# STSPIN32F0A_ESC2.net
KiCad netlist of a schematic drawn in Altium Designer
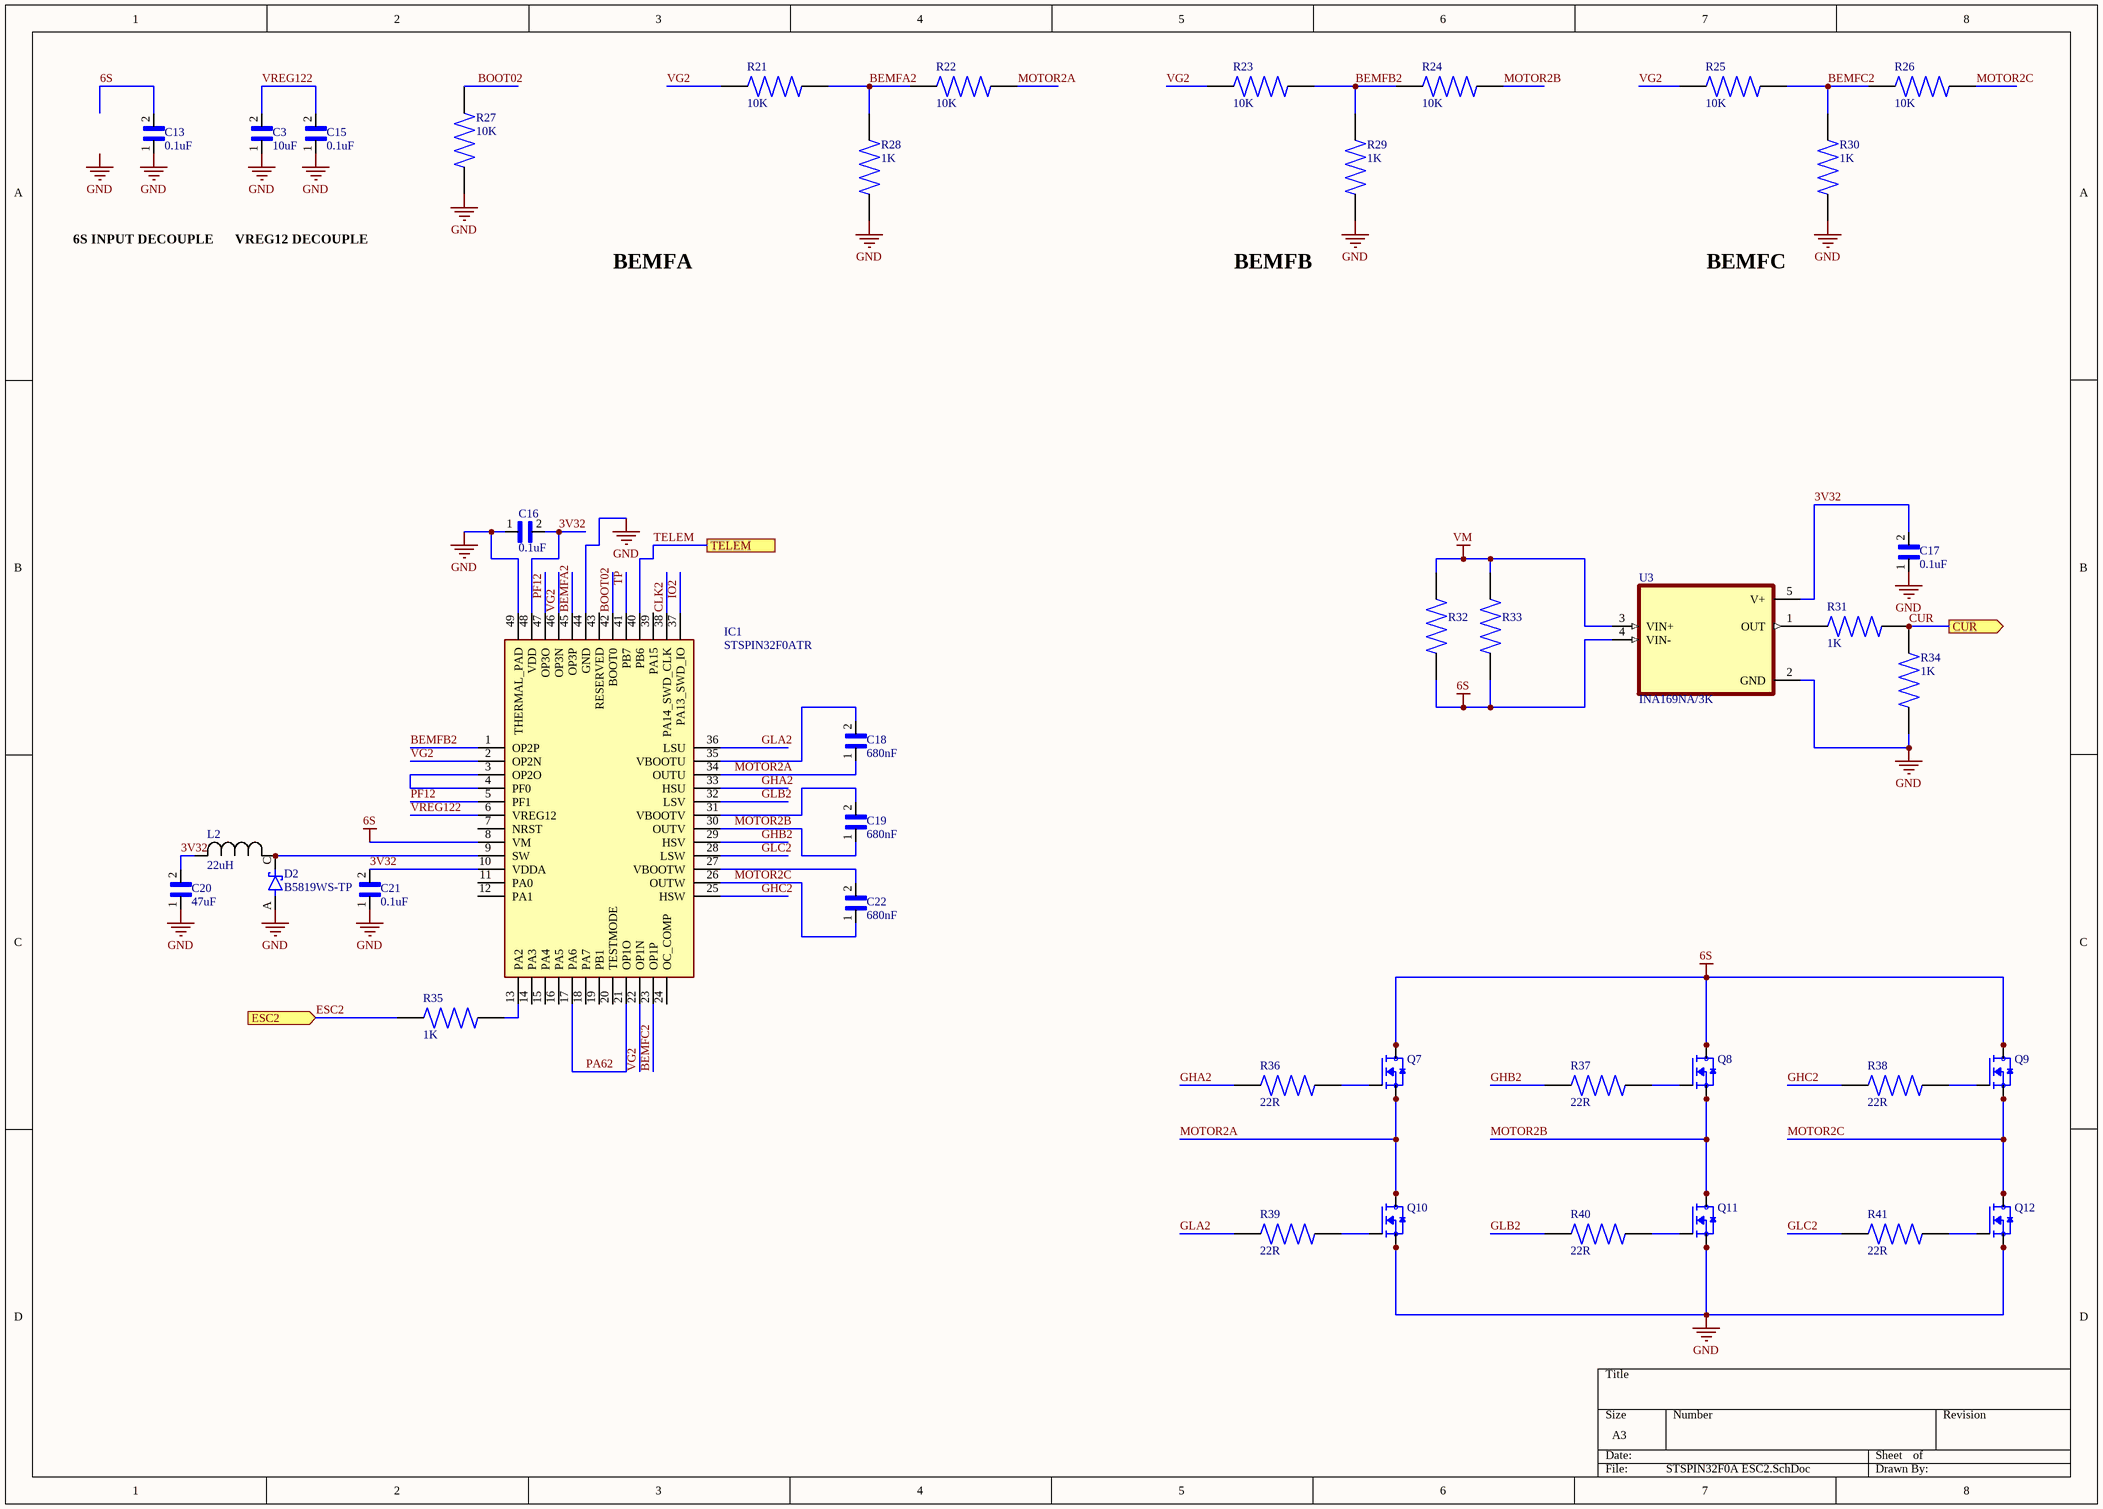
[diagram p0: STSPIN32F0A ESC2.SchDoc]

(export (version "E")
  (design (tool "Eeschema 10.0.6"))
  (components
    (comp (ref "C3")
      (value "10uF")
      (footprint "CAPC1608X90N")
      (description "SMD Capacitor X7R(EIA) with Capacitance: 0.22uF Tol. 5%. Rated Voltage: 25Vdc")
      (fields (field (name "MP") "GRM188R71E224JA88D"))
      (libsource (lib "GRM188R71E224JA88D") (part "GRM188R71E224JA88D"))
    )
    (comp (ref "C13")
      (value "0.1uF")
      (footprint "CAPC1005X55N")
      (fields (field (name "MP") "GRM1555C1H222JA01D"))
      (libsource (lib "GRM1555C1H222JA01D") (part "GRM1555C1H222JA01D"))
    )
    (comp (ref "C15")
      (value "0.1uF")
      (footprint "CAPC1005X55N")
      (fields (field (name "MP") "GRM1555C1H222JA01D"))
      (libsource (lib "GRM1555C1H222JA01D") (part "GRM1555C1H222JA01D"))
    )
    (comp (ref "C16")
      (value "0.1uF")
      (footprint "CAPC1005X55N")
      (fields (field (name "MP") "GRM1555C1H222JA01D"))
      (libsource (lib "") (part "GRM1555C1H222JA01D_1"))
    )
    (comp (ref "C17")
      (value "0.1uF")
      (footprint "CAPC1005X55N")
      (fields (field (name "MP") "GRM1555C1H222JA01D"))
      (libsource (lib "GRM1555C1H222JA01D") (part "GRM1555C1H222JA01D"))
    )
    (comp (ref "C18")
      (value "680nF")
      (footprint "CAPC1005X55N")
      (fields (field (name "MP") "GRM1555C1H222JA01D"))
      (libsource (lib "GRM1555C1H222JA01D") (part "GRM1555C1H222JA01D"))
    )
    (comp (ref "C19")
      (value "680nF")
      (footprint "CAPC1005X55N")
      (fields (field (name "MP") "GRM1555C1H222JA01D"))
      (libsource (lib "GRM1555C1H222JA01D") (part "GRM1555C1H222JA01D"))
    )
    (comp (ref "C20")
      (value "47uF")
      (footprint "CAPC1608X90N")
      (description "SMD Capacitor X7R(EIA) with Capacitance: 0.22uF Tol. 5%. Rated Voltage: 25Vdc")
      (fields (field (name "MP") "GRM188R71E224JA88D"))
      (libsource (lib "GRM188R71E224JA88D") (part "GRM188R71E224JA88D"))
    )
    (comp (ref "C21")
      (value "0.1uF")
      (footprint "CAPC1005X55N")
      (fields (field (name "MP") "GRM1555C1H222JA01D"))
      (libsource (lib "GRM1555C1H222JA01D") (part "GRM1555C1H222JA01D"))
    )
    (comp (ref "C22")
      (value "680nF")
      (footprint "CAPC1005X55N")
      (fields (field (name "MP") "GRM1555C1H222JA01D"))
      (libsource (lib "GRM1555C1H222JA01D") (part "GRM1555C1H222JA01D"))
    )
    (comp (ref "D2")
      (value "B5819WS-TP")
      (footprint "SOD2512X115N")
      (fields (field (name "MF") "{'manufacturer': u'Micro Commercial Components'}"))
      (libsource (lib "SnapEDA_Library") (part "B5819WS-TP"))
    )
    (comp (ref "IC1")
      (value "STSPIN32F0ATR")
      (footprint "SamacSys:QFN50P700X700X100-49N-D")
      (description "Integrated Circuit")
      (fields (field (name "MOUSER PART NUMBER") "511-STSPIN32F0ATR"))
      (libsource (lib "SamacSys") (part "STSPIN32F0ATR"))
    )
    (comp (ref "L2")
      (value "22uH")
      (footprint "IND_BOURNS_SRN3015")
      (description "No Description Available")
      (fields
        (field (name "MANUFACTURER_PART_NUMBER") "SRN3015-220M")
        (field (name "COPYRIGHT") "Copyright (C) 2022 Ultra Librarian. All rights reserved.")
      )
      (libsource (lib "SRN3015-220M") (part "SRN3015-220M"))
    )
    (comp (ref "Q7")
      (value "TPHR8504PL,L1Q")
      (footprint "TRANS_TPHR8504PL,L1Q")
      (description "N-Channel 40V 150A (Tc) 1W (Ta), 170W (Tc) Surface Mount 8-SOP Advance (5x5)")
      (fields (field (name "MF") "Toshiba Semiconductor"))
      (libsource (lib "TPHR8504PL_L1Q") (part "TPHR8504PL,L1Q"))
    )
    (comp (ref "Q8")
      (value "TPHR8504PL,L1Q")
      (footprint "TRANS_TPHR8504PL,L1Q")
      (description "N-Channel 40V 150A (Tc) 1W (Ta), 170W (Tc) Surface Mount 8-SOP Advance (5x5)")
      (fields (field (name "MF") "Toshiba Semiconductor"))
      (libsource (lib "TPHR8504PL_L1Q") (part "TPHR8504PL,L1Q"))
    )
    (comp (ref "Q9")
      (value "TPHR8504PL,L1Q")
      (footprint "TRANS_TPHR8504PL,L1Q")
      (description "N-Channel 40V 150A (Tc) 1W (Ta), 170W (Tc) Surface Mount 8-SOP Advance (5x5)")
      (fields (field (name "MF") "Toshiba Semiconductor"))
      (libsource (lib "TPHR8504PL_L1Q") (part "TPHR8504PL,L1Q"))
    )
    (comp (ref "Q10")
      (value "TPHR8504PL,L1Q")
      (footprint "TRANS_TPHR8504PL,L1Q")
      (description "N-Channel 40V 150A (Tc) 1W (Ta), 170W (Tc) Surface Mount 8-SOP Advance (5x5)")
      (fields (field (name "MF") "Toshiba Semiconductor"))
      (libsource (lib "TPHR8504PL_L1Q") (part "TPHR8504PL,L1Q"))
    )
    (comp (ref "Q11")
      (value "TPHR8504PL,L1Q")
      (footprint "TRANS_TPHR8504PL,L1Q")
      (description "N-Channel 40V 150A (Tc) 1W (Ta), 170W (Tc) Surface Mount 8-SOP Advance (5x5)")
      (fields (field (name "MF") "Toshiba Semiconductor"))
      (libsource (lib "TPHR8504PL_L1Q") (part "TPHR8504PL,L1Q"))
    )
    (comp (ref "Q12")
      (value "TPHR8504PL,L1Q")
      (footprint "TRANS_TPHR8504PL,L1Q")
      (description "N-Channel 40V 150A (Tc) 1W (Ta), 170W (Tc) Surface Mount 8-SOP Advance (5x5)")
      (fields (field (name "MF") "Toshiba Semiconductor"))
      (libsource (lib "TPHR8504PL_L1Q") (part "TPHR8504PL,L1Q"))
    )
    (comp (ref "R21")
      (value "10K")
      (footprint "RESC1005X37N")
      (fields (field (name "MP") "RE0402BRE07330KL") (field (name "MF") "{'manufacturer': u'Yageo'}"))
      (libsource (lib "SnapEDA_Library") (part "RE0402BRE07330KL"))
    )
    (comp (ref "R22")
      (value "10K")
      (footprint "RESC1005X37N")
      (fields (field (name "MP") "RE0402BRE07330KL") (field (name "MF") "{'manufacturer': u'Yageo'}"))
      (libsource (lib "SnapEDA_Library") (part "RE0402BRE07330KL"))
    )
    (comp (ref "R23")
      (value "10K")
      (footprint "RESC1005X37N")
      (fields (field (name "MP") "RE0402BRE07330KL") (field (name "MF") "{'manufacturer': u'Yageo'}"))
      (libsource (lib "SnapEDA_Library") (part "RE0402BRE07330KL"))
    )
    (comp (ref "R24")
      (value "10K")
      (footprint "RESC1005X37N")
      (fields (field (name "MP") "RE0402BRE07330KL") (field (name "MF") "{'manufacturer': u'Yageo'}"))
      (libsource (lib "SnapEDA_Library") (part "RE0402BRE07330KL"))
    )
    (comp (ref "R25")
      (value "10K")
      (footprint "RESC1005X37N")
      (fields (field (name "MP") "RE0402BRE07330KL") (field (name "MF") "{'manufacturer': u'Yageo'}"))
      (libsource (lib "SnapEDA_Library") (part "RE0402BRE07330KL"))
    )
    (comp (ref "R26")
      (value "10K")
      (footprint "RESC1005X37N")
      (fields (field (name "MP") "RE0402BRE07330KL") (field (name "MF") "{'manufacturer': u'Yageo'}"))
      (libsource (lib "SnapEDA_Library") (part "RE0402BRE07330KL"))
    )
    (comp (ref "R27")
      (value "10K")
      (footprint "RESC1005X37N")
      (fields (field (name "MP") "RE0402BRE07330KL") (field (name "MF") "{'manufacturer': u'Yageo'}"))
      (libsource (lib "SnapEDA_Library") (part "RE0402BRE07330KL"))
    )
    (comp (ref "R28")
      (value "1K")
      (footprint "RESC1005X37N")
      (fields (field (name "MP") "RE0402BRE07330KL") (field (name "MF") "{'manufacturer': u'Yageo'}"))
      (libsource (lib "SnapEDA_Library") (part "RE0402BRE07330KL"))
    )
    (comp (ref "R29")
      (value "1K")
      (footprint "RESC1005X37N")
      (fields (field (name "MP") "RE0402BRE07330KL") (field (name "MF") "{'manufacturer': u'Yageo'}"))
      (libsource (lib "SnapEDA_Library") (part "RE0402BRE07330KL"))
    )
    (comp (ref "R30")
      (value "1K")
      (footprint "RESC1005X37N")
      (fields (field (name "MP") "RE0402BRE07330KL") (field (name "MF") "{'manufacturer': u'Yageo'}"))
      (libsource (lib "SnapEDA_Library") (part "RE0402BRE07330KL"))
    )
    (comp (ref "R31")
      (value "1K")
      (footprint "RESC1005X37N")
      (fields (field (name "MP") "RE0402BRE07330KL") (field (name "MF") "{'manufacturer': u'Yageo'}"))
      (libsource (lib "SnapEDA_Library") (part "RE0402BRE07330KL"))
    )
    (comp (ref "R32")
      (value "CSSH2512JTL500")
      (footprint "RESC6232X104N")
      (fields (field (name "MF") "{'manufacturer': u'Stackpole Electronics Inc'}"))
      (libsource (lib "SnapEDA_Library") (part "CSSH2512JTL500"))
    )
    (comp (ref "R33")
      (value "CSSH2512JTL500")
      (footprint "RESC6232X104N")
      (fields (field (name "MF") "{'manufacturer': u'Stackpole Electronics Inc'}"))
      (libsource (lib "SnapEDA_Library") (part "CSSH2512JTL500"))
    )
    (comp (ref "R34")
      (value "1K")
      (footprint "RESC1005X37N")
      (fields (field (name "MP") "RE0402BRE07330KL") (field (name "MF") "{'manufacturer': u'Yageo'}"))
      (libsource (lib "SnapEDA_Library") (part "RE0402BRE07330KL"))
    )
    (comp (ref "R35")
      (value "1K")
      (footprint "RESC1005X37N")
      (fields (field (name "MP") "RE0402BRE07330KL") (field (name "MF") "{'manufacturer': u'Yageo'}"))
      (libsource (lib "SnapEDA_Library") (part "RE0402BRE07330KL"))
    )
    (comp (ref "R36")
      (value "22R")
      (footprint "RESC1005X37N")
      (fields (field (name "MP") "RE0402BRE07330KL") (field (name "MF") "{'manufacturer': u'Yageo'}"))
      (libsource (lib "SnapEDA_Library") (part "RE0402BRE07330KL"))
    )
    (comp (ref "R37")
      (value "22R")
      (footprint "RESC1005X37N")
      (fields (field (name "MP") "RE0402BRE07330KL") (field (name "MF") "{'manufacturer': u'Yageo'}"))
      (libsource (lib "SnapEDA_Library") (part "RE0402BRE07330KL"))
    )
    (comp (ref "R38")
      (value "22R")
      (footprint "RESC1005X37N")
      (fields (field (name "MP") "RE0402BRE07330KL") (field (name "MF") "{'manufacturer': u'Yageo'}"))
      (libsource (lib "SnapEDA_Library") (part "RE0402BRE07330KL"))
    )
    (comp (ref "R39")
      (value "22R")
      (footprint "RESC1005X37N")
      (fields (field (name "MP") "RE0402BRE07330KL") (field (name "MF") "{'manufacturer': u'Yageo'}"))
      (libsource (lib "SnapEDA_Library") (part "RE0402BRE07330KL"))
    )
    (comp (ref "R40")
      (value "22R")
      (footprint "RESC1005X37N")
      (fields (field (name "MP") "RE0402BRE07330KL") (field (name "MF") "{'manufacturer': u'Yageo'}"))
      (libsource (lib "SnapEDA_Library") (part "RE0402BRE07330KL"))
    )
    (comp (ref "R41")
      (value "22R")
      (footprint "RESC1005X37N")
      (fields (field (name "MP") "RE0402BRE07330KL") (field (name "MF") "{'manufacturer': u'Yageo'}"))
      (libsource (lib "SnapEDA_Library") (part "RE0402BRE07330KL"))
    )
    (comp (ref "U3")
      (value "INA169NA/3K")
      (footprint "SOT95P280X145-5N")
      (fields (field (name "MF") "{'manufacturer': u'Texas Instruments'}"))
      (libsource (lib "SnapEDA_Library") (part "INA169NA/3K"))
    )
  )
  (nets
    (net (code "1") (name "/3V32") (class "Default")
      (node (ref "C16") (pin "2") (pinfunction "2_2") (pintype "passive"))
      (node (ref "C17") (pin "2") (pinfunction "2_2") (pintype "passive"))
      (node (ref "C20") (pin "2") (pinfunction "2_2") (pintype "passive"))
      (node (ref "C21") (pin "2") (pinfunction "2_2") (pintype "passive"))
      (node (ref "IC1") (pin "10") (pinfunction "VDDA_10") (pintype "passive"))
      (node (ref "IC1") (pin "48") (pinfunction "VDD_48") (pintype "passive"))
      (node (ref "L2") (pin "2") (pinfunction "2_2") (pintype "passive"))
      (node (ref "U3") (pin "5") (pinfunction "V+_5") (pintype "power_in"))
    )
    (net (code "2") (name "/BEMFA2") (class "Default")
      (node (ref "IC1") (pin "45") (pinfunction "OP3P_45") (pintype "passive"))
      (node (ref "R21") (pin "1") (pinfunction "1_1") (pintype "passive"))
      (node (ref "R22") (pin "2") (pinfunction "2_2") (pintype "passive"))
      (node (ref "R28") (pin "1") (pinfunction "1_1") (pintype "passive"))
    )
    (net (code "3") (name "/BEMFB2") (class "Default")
      (node (ref "IC1") (pin "1") (pinfunction "OP2P_1") (pintype "passive"))
      (node (ref "R23") (pin "1") (pinfunction "1_1") (pintype "passive"))
      (node (ref "R24") (pin "2") (pinfunction "2_2") (pintype "passive"))
      (node (ref "R29") (pin "1") (pinfunction "1_1") (pintype "passive"))
    )
    (net (code "4") (name "/BEMFC2") (class "Default")
      (node (ref "IC1") (pin "23") (pinfunction "OP1P_23") (pintype "passive"))
      (node (ref "R25") (pin "1") (pinfunction "1_1") (pintype "passive"))
      (node (ref "R26") (pin "2") (pinfunction "2_2") (pintype "passive"))
      (node (ref "R30") (pin "1") (pinfunction "1_1") (pintype "passive"))
    )
    (net (code "5") (name "/BOOT02") (class "Default")
      (node (ref "IC1") (pin "42") (pinfunction "BOOT0_42") (pintype "passive"))
      (node (ref "R27") (pin "2") (pinfunction "2_2") (pintype "passive"))
    )
    (net (code "6") (name "/CLK2") (class "Default")
      (node (ref "IC1") (pin "38") (pinfunction "PA14_SWD_CLK_38") (pintype "passive"))
    )
    (net (code "7") (name "/CUR") (class "Default")
      (node (ref "R31") (pin "2") (pinfunction "2_2") (pintype "passive"))
      (node (ref "R34") (pin "1") (pinfunction "1_1") (pintype "passive"))
    )
    (net (code "8") (name "/ESC2") (class "Default")
      (node (ref "R35") (pin "1") (pinfunction "1_1") (pintype "passive"))
    )
    (net (code "9") (name "/GHA2") (class "Default")
      (node (ref "IC1") (pin "33") (pinfunction "HSU_33") (pintype "passive"))
      (node (ref "R36") (pin "2") (pinfunction "2_2") (pintype "passive"))
    )
    (net (code "10") (name "/GHB2") (class "Default")
      (node (ref "IC1") (pin "29") (pinfunction "HSV_29") (pintype "passive"))
      (node (ref "R37") (pin "2") (pinfunction "2_2") (pintype "passive"))
    )
    (net (code "11") (name "/GHC2") (class "Default")
      (node (ref "IC1") (pin "25") (pinfunction "HSW_25") (pintype "passive"))
      (node (ref "R38") (pin "2") (pinfunction "2_2") (pintype "passive"))
    )
    (net (code "12") (name "/GLA2") (class "Default")
      (node (ref "IC1") (pin "36") (pinfunction "LSU_36") (pintype "passive"))
      (node (ref "R39") (pin "2") (pinfunction "2_2") (pintype "passive"))
    )
    (net (code "13") (name "/GLB2") (class "Default")
      (node (ref "IC1") (pin "32") (pinfunction "LSV_32") (pintype "passive"))
      (node (ref "R40") (pin "2") (pinfunction "2_2") (pintype "passive"))
    )
    (net (code "14") (name "/GLC2") (class "Default")
      (node (ref "IC1") (pin "28") (pinfunction "LSW_28") (pintype "passive"))
      (node (ref "R41") (pin "2") (pinfunction "2_2") (pintype "passive"))
    )
    (net (code "15") (name "/IO2") (class "Default")
      (node (ref "IC1") (pin "37") (pinfunction "PA13_SWD_IO_37") (pintype "passive"))
    )
    (net (code "16") (name "/MOTOR2A") (class "Default")
      (node (ref "C18") (pin "1") (pinfunction "1_1") (pintype "passive"))
      (node (ref "IC1") (pin "34") (pinfunction "OUTU_34") (pintype "passive"))
      (node (ref "Q10") (pin "5") (pinfunction "D_5") (pintype "passive"))
      (node (ref "Q10") (pin "6") (pinfunction "D_6") (pintype "passive"))
      (node (ref "Q10") (pin "7") (pinfunction "D_7") (pintype "passive"))
      (node (ref "Q10") (pin "8") (pinfunction "D_8") (pintype "passive"))
      (node (ref "Q10") (pin "9") (pinfunction "D_9") (pintype "passive"))
      (node (ref "Q7") (pin "1") (pinfunction "S_1") (pintype "passive"))
      (node (ref "Q7") (pin "2") (pinfunction "S_2") (pintype "passive"))
      (node (ref "Q7") (pin "3") (pinfunction "S_3") (pintype "passive"))
      (node (ref "R22") (pin "1") (pinfunction "1_1") (pintype "passive"))
    )
    (net (code "17") (name "/MOTOR2B") (class "Default")
      (node (ref "C19") (pin "1") (pinfunction "1_1") (pintype "passive"))
      (node (ref "IC1") (pin "30") (pinfunction "OUTV_30") (pintype "passive"))
      (node (ref "Q11") (pin "5") (pinfunction "D_5") (pintype "passive"))
      (node (ref "Q11") (pin "6") (pinfunction "D_6") (pintype "passive"))
      (node (ref "Q11") (pin "7") (pinfunction "D_7") (pintype "passive"))
      (node (ref "Q11") (pin "8") (pinfunction "D_8") (pintype "passive"))
      (node (ref "Q11") (pin "9") (pinfunction "D_9") (pintype "passive"))
      (node (ref "Q8") (pin "1") (pinfunction "S_1") (pintype "passive"))
      (node (ref "Q8") (pin "2") (pinfunction "S_2") (pintype "passive"))
      (node (ref "Q8") (pin "3") (pinfunction "S_3") (pintype "passive"))
      (node (ref "R24") (pin "1") (pinfunction "1_1") (pintype "passive"))
    )
    (net (code "18") (name "/MOTOR2C") (class "Default")
      (node (ref "C22") (pin "1") (pinfunction "1_1") (pintype "passive"))
      (node (ref "IC1") (pin "26") (pinfunction "OUTW_26") (pintype "passive"))
      (node (ref "Q12") (pin "5") (pinfunction "D_5") (pintype "passive"))
      (node (ref "Q12") (pin "6") (pinfunction "D_6") (pintype "passive"))
      (node (ref "Q12") (pin "7") (pinfunction "D_7") (pintype "passive"))
      (node (ref "Q12") (pin "8") (pinfunction "D_8") (pintype "passive"))
      (node (ref "Q12") (pin "9") (pinfunction "D_9") (pintype "passive"))
      (node (ref "Q9") (pin "1") (pinfunction "S_1") (pintype "passive"))
      (node (ref "Q9") (pin "2") (pinfunction "S_2") (pintype "passive"))
      (node (ref "Q9") (pin "3") (pinfunction "S_3") (pintype "passive"))
      (node (ref "R26") (pin "1") (pinfunction "1_1") (pintype "passive"))
    )
    (net (code "19") (name "/PA62") (class "Default")
      (node (ref "IC1") (pin "17") (pinfunction "PA6_17") (pintype "passive"))
      (node (ref "IC1") (pin "21") (pinfunction "OP1O_21") (pintype "passive"))
    )
    (net (code "20") (name "/PF12") (class "Default")
      (node (ref "IC1") (pin "47") (pinfunction "OP3O_47") (pintype "passive"))
      (node (ref "IC1") (pin "5") (pinfunction "PF1_5") (pintype "passive"))
    )
    (net (code "21") (name "/TELEM") (class "Default")
      (node (ref "IC1") (pin "40") (pinfunction "PB6_40") (pintype "passive"))
    )
    (net (code "22") (name "/TP") (class "Default")
      (node (ref "IC1") (pin "41") (pinfunction "PB7_41") (pintype "passive"))
    )
    (net (code "23") (name "/VG2") (class "Default")
      (node (ref "IC1") (pin "2") (pinfunction "OP2N_2") (pintype "passive"))
      (node (ref "IC1") (pin "22") (pinfunction "OP1N_22") (pintype "passive"))
      (node (ref "IC1") (pin "46") (pinfunction "OP3N_46") (pintype "passive"))
      (node (ref "R21") (pin "2") (pinfunction "2_2") (pintype "passive"))
      (node (ref "R23") (pin "2") (pinfunction "2_2") (pintype "passive"))
      (node (ref "R25") (pin "2") (pinfunction "2_2") (pintype "passive"))
    )
    (net (code "24") (name "/VREG122") (class "Default")
      (node (ref "C15") (pin "2") (pinfunction "2_2") (pintype "passive"))
      (node (ref "C3") (pin "2") (pinfunction "2_2") (pintype "passive"))
      (node (ref "IC1") (pin "6") (pinfunction "VREG12_6") (pintype "passive"))
    )
    (net (code "25") (name "6S") (class "Default")
      (node (ref "C13") (pin "2") (pinfunction "2_2") (pintype "passive"))
      (node (ref "IC1") (pin "8") (pinfunction "VM_8") (pintype "passive"))
      (node (ref "Q7") (pin "5") (pinfunction "D_5") (pintype "passive"))
      (node (ref "Q7") (pin "6") (pinfunction "D_6") (pintype "passive"))
      (node (ref "Q7") (pin "7") (pinfunction "D_7") (pintype "passive"))
      (node (ref "Q7") (pin "8") (pinfunction "D_8") (pintype "passive"))
      (node (ref "Q7") (pin "9") (pinfunction "D_9") (pintype "passive"))
      (node (ref "Q8") (pin "5") (pinfunction "D_5") (pintype "passive"))
      (node (ref "Q8") (pin "6") (pinfunction "D_6") (pintype "passive"))
      (node (ref "Q8") (pin "7") (pinfunction "D_7") (pintype "passive"))
      (node (ref "Q8") (pin "8") (pinfunction "D_8") (pintype "passive"))
      (node (ref "Q8") (pin "9") (pinfunction "D_9") (pintype "passive"))
      (node (ref "Q9") (pin "5") (pinfunction "D_5") (pintype "passive"))
      (node (ref "Q9") (pin "6") (pinfunction "D_6") (pintype "passive"))
      (node (ref "Q9") (pin "7") (pinfunction "D_7") (pintype "passive"))
      (node (ref "Q9") (pin "8") (pinfunction "D_8") (pintype "passive"))
      (node (ref "Q9") (pin "9") (pinfunction "D_9") (pintype "passive"))
      (node (ref "R32") (pin "2") (pinfunction "2_2") (pintype "passive"))
      (node (ref "R33") (pin "2") (pinfunction "2_2") (pintype "passive"))
      (node (ref "U3") (pin "4") (pinfunction "VIN-_4") (pintype "input"))
    )
    (net (code "26") (name "GND") (class "Default")
      (node (ref "C13") (pin "1") (pinfunction "1_1") (pintype "passive"))
      (node (ref "C15") (pin "1") (pinfunction "1_1") (pintype "passive"))
      (node (ref "C16") (pin "1") (pinfunction "1_1") (pintype "passive"))
      (node (ref "C17") (pin "1") (pinfunction "1_1") (pintype "passive"))
      (node (ref "C20") (pin "1") (pinfunction "1_1") (pintype "passive"))
      (node (ref "C21") (pin "1") (pinfunction "1_1") (pintype "passive"))
      (node (ref "C3") (pin "1") (pinfunction "1_1") (pintype "passive"))
      (node (ref "D2") (pin "A") (pinfunction "A_A") (pintype "passive"))
      (node (ref "IC1") (pin "44") (pinfunction "GND_44") (pintype "passive"))
      (node (ref "IC1") (pin "49") (pinfunction "THERMAL_PAD_49") (pintype "passive"))
      (node (ref "Q10") (pin "1") (pinfunction "S_1") (pintype "passive"))
      (node (ref "Q10") (pin "2") (pinfunction "S_2") (pintype "passive"))
      (node (ref "Q10") (pin "3") (pinfunction "S_3") (pintype "passive"))
      (node (ref "Q11") (pin "1") (pinfunction "S_1") (pintype "passive"))
      (node (ref "Q11") (pin "2") (pinfunction "S_2") (pintype "passive"))
      (node (ref "Q11") (pin "3") (pinfunction "S_3") (pintype "passive"))
      (node (ref "Q12") (pin "1") (pinfunction "S_1") (pintype "passive"))
      (node (ref "Q12") (pin "2") (pinfunction "S_2") (pintype "passive"))
      (node (ref "Q12") (pin "3") (pinfunction "S_3") (pintype "passive"))
      (node (ref "R27") (pin "1") (pinfunction "1_1") (pintype "passive"))
      (node (ref "R28") (pin "2") (pinfunction "2_2") (pintype "passive"))
      (node (ref "R29") (pin "2") (pinfunction "2_2") (pintype "passive"))
      (node (ref "R30") (pin "2") (pinfunction "2_2") (pintype "passive"))
      (node (ref "R34") (pin "2") (pinfunction "2_2") (pintype "passive"))
      (node (ref "U3") (pin "2") (pinfunction "GND_2") (pintype "power_in"))
    )
    (net (code "27") (name "Net-(D2-K)") (class "Default")
      (node (ref "D2") (pin "C") (pinfunction "K_C") (pintype "passive"))
      (node (ref "IC1") (pin "9") (pinfunction "SW_9") (pintype "passive"))
      (node (ref "L2") (pin "1") (pinfunction "1_1") (pintype "passive"))
    )
    (net (code "28") (name "Net-(IC1-OP2O)") (class "Default")
      (node (ref "IC1") (pin "3") (pinfunction "OP2O_3") (pintype "passive"))
      (node (ref "IC1") (pin "4") (pinfunction "PF0_4") (pintype "passive"))
    )
    (net (code "29") (name "Net-(IC1-PA2)") (class "Default")
      (node (ref "IC1") (pin "13") (pinfunction "PA2_13") (pintype "passive"))
      (node (ref "R35") (pin "2") (pinfunction "2_2") (pintype "passive"))
    )
    (net (code "30") (name "Net-(IC1-VBOOTU)") (class "Default")
      (node (ref "C18") (pin "2") (pinfunction "2_2") (pintype "passive"))
      (node (ref "IC1") (pin "35") (pinfunction "VBOOTU_35") (pintype "passive"))
    )
    (net (code "31") (name "Net-(IC1-VBOOTV)") (class "Default")
      (node (ref "C19") (pin "2") (pinfunction "2_2") (pintype "passive"))
      (node (ref "IC1") (pin "31") (pinfunction "VBOOTV_31") (pintype "passive"))
    )
    (net (code "32") (name "Net-(IC1-VBOOTW)") (class "Default")
      (node (ref "C22") (pin "2") (pinfunction "2_2") (pintype "passive"))
      (node (ref "IC1") (pin "27") (pinfunction "VBOOTW_27") (pintype "passive"))
    )
    (net (code "33") (name "Net-(Q7-G)") (class "Default")
      (node (ref "Q7") (pin "4") (pinfunction "G_4") (pintype "passive"))
      (node (ref "R36") (pin "1") (pinfunction "1_1") (pintype "passive"))
    )
    (net (code "34") (name "Net-(Q8-G)") (class "Default")
      (node (ref "Q8") (pin "4") (pinfunction "G_4") (pintype "passive"))
      (node (ref "R37") (pin "1") (pinfunction "1_1") (pintype "passive"))
    )
    (net (code "35") (name "Net-(Q9-G)") (class "Default")
      (node (ref "Q9") (pin "4") (pinfunction "G_4") (pintype "passive"))
      (node (ref "R38") (pin "1") (pinfunction "1_1") (pintype "passive"))
    )
    (net (code "36") (name "Net-(Q10-G)") (class "Default")
      (node (ref "Q10") (pin "4") (pinfunction "G_4") (pintype "passive"))
      (node (ref "R39") (pin "1") (pinfunction "1_1") (pintype "passive"))
    )
    (net (code "37") (name "Net-(Q11-G)") (class "Default")
      (node (ref "Q11") (pin "4") (pinfunction "G_4") (pintype "passive"))
      (node (ref "R40") (pin "1") (pinfunction "1_1") (pintype "passive"))
    )
    (net (code "38") (name "Net-(Q12-G)") (class "Default")
      (node (ref "Q12") (pin "4") (pinfunction "G_4") (pintype "passive"))
      (node (ref "R41") (pin "1") (pinfunction "1_1") (pintype "passive"))
    )
    (net (code "39") (name "Net-(U3-OUT)") (class "Default")
      (node (ref "R31") (pin "1") (pinfunction "1_1") (pintype "passive"))
      (node (ref "U3") (pin "1") (pinfunction "OUT_1") (pintype "output"))
    )
    (net (code "40") (name "VM") (class "Default")
      (node (ref "R32") (pin "1") (pinfunction "1_1") (pintype "passive"))
      (node (ref "R33") (pin "1") (pinfunction "1_1") (pintype "passive"))
      (node (ref "U3") (pin "3") (pinfunction "VIN+_3") (pintype "input"))
    )
    (net (code "41") (name "unconnected-(IC1-NRST-Pad7)") (class "Default")
      (node (ref "IC1") (pin "7") (pinfunction "NRST_7") (pintype "passive"))
    )
    (net (code "42") (name "unconnected-(IC1-OC_COMP-Pad24)") (class "Default")
      (node (ref "IC1") (pin "24") (pinfunction "OC_COMP_24") (pintype "passive"))
    )
    (net (code "43") (name "unconnected-(IC1-PA0-Pad11)") (class "Default")
      (node (ref "IC1") (pin "11") (pinfunction "PA0_11") (pintype "passive"))
    )
    (net (code "44") (name "unconnected-(IC1-PA1-Pad12)") (class "Default")
      (node (ref "IC1") (pin "12") (pinfunction "PA1_12") (pintype "passive"))
    )
    (net (code "45") (name "unconnected-(IC1-PA3-Pad14)") (class "Default")
      (node (ref "IC1") (pin "14") (pinfunction "PA3_14") (pintype "passive"))
    )
    (net (code "46") (name "unconnected-(IC1-PA4-Pad15)") (class "Default")
      (node (ref "IC1") (pin "15") (pinfunction "PA4_15") (pintype "passive"))
    )
    (net (code "47") (name "unconnected-(IC1-PA5-Pad16)") (class "Default")
      (node (ref "IC1") (pin "16") (pinfunction "PA5_16") (pintype "passive"))
    )
    (net (code "48") (name "unconnected-(IC1-PA7-Pad18)") (class "Default")
      (node (ref "IC1") (pin "18") (pinfunction "PA7_18") (pintype "passive"))
    )
    (net (code "49") (name "unconnected-(IC1-PA15-Pad39)") (class "Default")
      (node (ref "IC1") (pin "39") (pinfunction "PA15_39") (pintype "passive"))
    )
    (net (code "50") (name "unconnected-(IC1-PB1-Pad19)") (class "Default")
      (node (ref "IC1") (pin "19") (pinfunction "PB1_19") (pintype "passive"))
    )
    (net (code "51") (name "unconnected-(IC1-RESERVED-Pad43)") (class "Default")
      (node (ref "IC1") (pin "43") (pinfunction "RESERVED_43") (pintype "passive"))
    )
    (net (code "52") (name "unconnected-(IC1-TESTMODE-Pad20)") (class "Default")
      (node (ref "IC1") (pin "20") (pinfunction "TESTMODE_20") (pintype "passive"))
    )
  )
)
